# STl-Link-V01.net
KiCad netlist of a schematic drawn in EAGLE
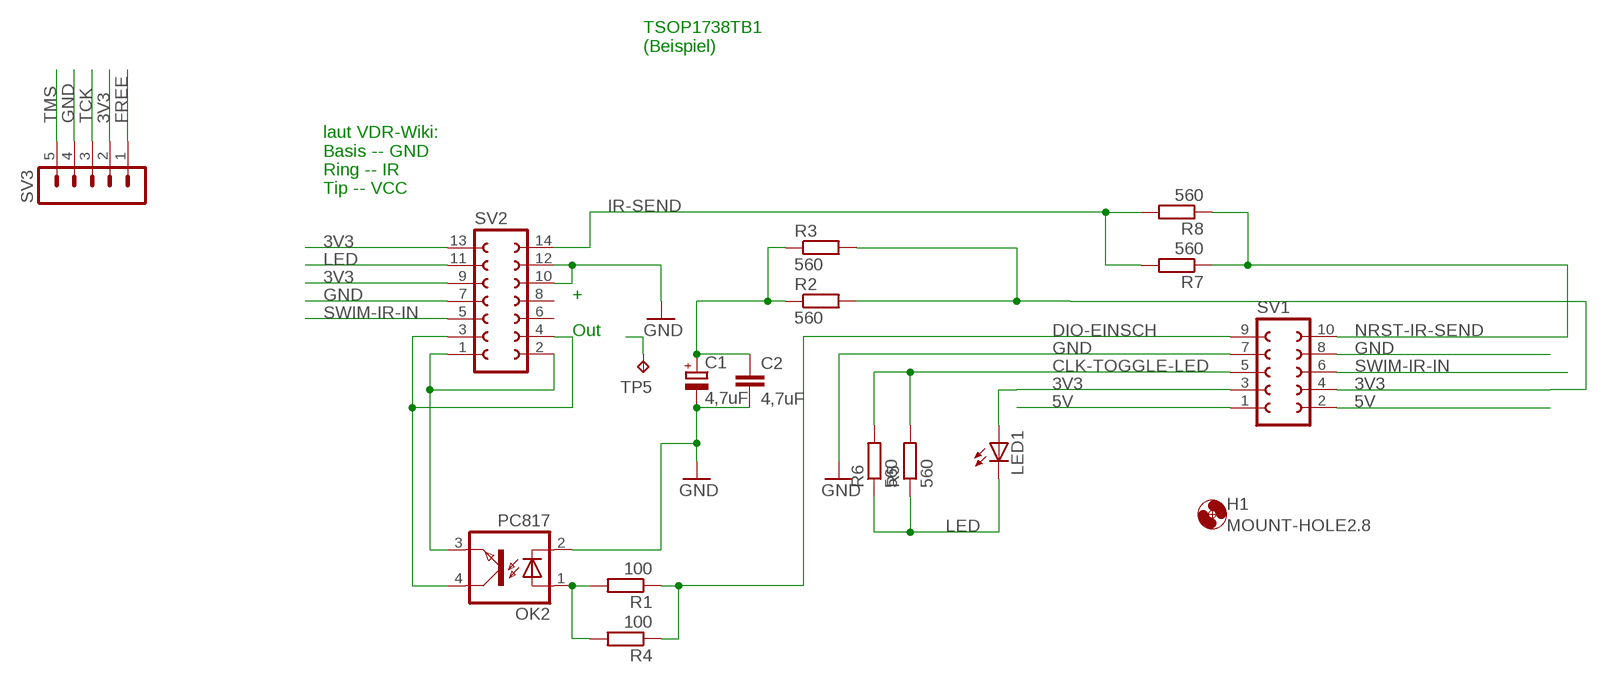
[diagram p0: schematic, sheet 1]

(export (version "E")
  (design (tool "Eeschema 10.0.6"))
  (components
    (comp (ref "C1")
      (value "4,7uF")
      (footprint "eagle-import:E1,8-4")
      (libsource (lib "eagle-import") (part "CPOL-EUE1.8-4"))
    )
    (comp (ref "C2")
      (value "4,7uF")
      (footprint "eagle-import:C1206K")
      (libsource (lib "eagle-import") (part "C-EUC1206K"))
    )
    (comp (ref "H1")
      (value "MOUNT-HOLE2.8")
      (footprint "eagle-import:2,8")
      (libsource (lib "eagle-import") (part "MOUNT-HOLE2.8"))
    )
    (comp (ref "LED1")
      (value "LEDCHIPLED_1206")
      (footprint "eagle-import:CHIPLED_1206")
      (libsource (lib "eagle-import") (part "LEDCHIPLED_1206"))
    )
    (comp (ref "OK2")
      (value "PC817")
      (footprint "eagle-import:DIL04")
      (fields (field (name "MPN") "PC817X4J000F"))
      (libsource (lib "eagle-import") (part "PC817"))
    )
    (comp (ref "R1")
      (value "100")
      (footprint "eagle-import:0204_7")
      (libsource (lib "eagle-import") (part "R-EU_0204/7"))
    )
    (comp (ref "R2")
      (value "560")
      (footprint "eagle-import:0204_7")
      (libsource (lib "eagle-import") (part "R-EU_0204/7"))
    )
    (comp (ref "R3")
      (value "560")
      (footprint "eagle-import:R0805W")
      (libsource (lib "eagle-import") (part "R-EU_R0805W"))
    )
    (comp (ref "R4")
      (value "100")
      (footprint "eagle-import:R0805W")
      (libsource (lib "eagle-import") (part "R-EU_R0805W"))
    )
    (comp (ref "R5")
      (value "560")
      (footprint "eagle-import:0204_7")
      (libsource (lib "eagle-import") (part "R-EU_0204/7"))
    )
    (comp (ref "R6")
      (value "560")
      (footprint "eagle-import:R0805W")
      (libsource (lib "eagle-import") (part "R-EU_R0805W"))
    )
    (comp (ref "R7")
      (value "560")
      (footprint "eagle-import:0204_7")
      (libsource (lib "eagle-import") (part "R-EU_0204/7"))
    )
    (comp (ref "R8")
      (value "560")
      (footprint "eagle-import:R0805W")
      (libsource (lib "eagle-import") (part "R-EU_R0805W"))
    )
    (comp (ref "SV1")
      (value "FE05-2")
      (footprint "eagle-import:FE05-2")
      (libsource (lib "eagle-import") (part "FE05-2"))
    )
    (comp (ref "SV2")
      (value "FE07-2W")
      (footprint "eagle-import:FE07-2W")
      (libsource (lib "eagle-import") (part "FE07-2W"))
    )
    (comp (ref "SV3")
      (value "MAR05-1")
      (footprint "eagle-import:MAR05-1")
      (libsource (lib "eagle-import") (part "MAR05-1"))
    )
    (comp (ref "TP5")
      (value "TPB1,27")
      (footprint "eagle-import:B1,27")
      (libsource (lib "eagle-import") (part "TPB1,27"))
    )
  )
  (nets
    (net (code "1") (name "/3V3") (class "Default")
      (node (ref "LED1") (pin "A") (pinfunction "A_A") (pintype "passive"))
      (node (ref "R2") (pin "2") (pinfunction "2_2") (pintype "passive"))
      (node (ref "R3") (pin "2") (pinfunction "2_2") (pintype "passive"))
      (node (ref "SV1") (pin "3") (pinfunction "3_3") (pintype "passive"))
      (node (ref "SV1") (pin "4") (pinfunction "4_4") (pintype "passive"))
      (node (ref "SV2") (pin "13") (pinfunction "13_13") (pintype "passive"))
      (node (ref "SV2") (pin "9") (pinfunction "9_9") (pintype "passive"))
      (node (ref "SV3") (pin "2") (pinfunction "2_2") (pintype "passive"))
    )
    (net (code "2") (name "/5V") (class "Default")
      (node (ref "SV1") (pin "1") (pinfunction "1_1") (pintype "passive"))
      (node (ref "SV1") (pin "2") (pinfunction "2_2") (pintype "passive"))
    )
    (net (code "3") (name "/CLK-TOGGLE-LED") (class "Default")
      (node (ref "R5") (pin "2") (pinfunction "2_2") (pintype "passive"))
      (node (ref "R6") (pin "2") (pinfunction "2_2") (pintype "passive"))
      (node (ref "SV1") (pin "5") (pinfunction "5_5") (pintype "passive"))
    )
    (net (code "4") (name "/DIO-EINSCH") (class "Default")
      (node (ref "R1") (pin "1") (pinfunction "1_1") (pintype "passive"))
      (node (ref "R4") (pin "1") (pinfunction "1_1") (pintype "passive"))
      (node (ref "SV1") (pin "9") (pinfunction "9_9") (pintype "passive"))
    )
    (net (code "5") (name "/FREE") (class "Default")
      (node (ref "SV3") (pin "1") (pinfunction "1_1") (pintype "passive"))
    )
    (net (code "6") (name "/IR-SEND") (class "Default")
      (node (ref "R7") (pin "2") (pinfunction "2_2") (pintype "passive"))
      (node (ref "R8") (pin "2") (pinfunction "2_2") (pintype "passive"))
      (node (ref "SV2") (pin "14") (pinfunction "14_14") (pintype "passive"))
    )
    (net (code "7") (name "/LED") (class "Default")
      (node (ref "LED1") (pin "C") (pinfunction "C_C") (pintype "passive"))
      (node (ref "R5") (pin "1") (pinfunction "1_1") (pintype "passive"))
      (node (ref "R6") (pin "1") (pinfunction "1_1") (pintype "passive"))
      (node (ref "SV2") (pin "11") (pinfunction "11_11") (pintype "passive"))
    )
    (net (code "8") (name "/NRST-IR-SEND") (class "Default")
      (node (ref "R7") (pin "1") (pinfunction "1_1") (pintype "passive"))
      (node (ref "R8") (pin "1") (pinfunction "1_1") (pintype "passive"))
      (node (ref "SV1") (pin "10") (pinfunction "10_10") (pintype "passive"))
    )
    (net (code "9") (name "/SWIM-IR-IN") (class "Default")
      (node (ref "SV1") (pin "6") (pinfunction "6_6") (pintype "passive"))
      (node (ref "SV2") (pin "5") (pinfunction "5_5") (pintype "passive"))
      (node (ref "TP5") (pin "TP") (pinfunction "TP_TP") (pintype "input"))
    )
    (net (code "10") (name "/TCK") (class "Default")
      (node (ref "SV3") (pin "3") (pinfunction "3_3") (pintype "passive"))
    )
    (net (code "11") (name "/TMS") (class "Default")
      (node (ref "SV3") (pin "5") (pinfunction "5_5") (pintype "passive"))
    )
    (net (code "12") (name "GND") (class "Default")
      (node (ref "C1") (pin "-") (pinfunction "-_-") (pintype "passive"))
      (node (ref "C2") (pin "2") (pinfunction "2_2") (pintype "passive"))
      (node (ref "OK2") (pin "2") (pinfunction "C_2") (pintype "passive"))
      (node (ref "SV1") (pin "7") (pinfunction "7_7") (pintype "passive"))
      (node (ref "SV1") (pin "8") (pinfunction "8_8") (pintype "passive"))
      (node (ref "SV2") (pin "10") (pinfunction "10_10") (pintype "passive"))
      (node (ref "SV2") (pin "12") (pinfunction "12_12") (pintype "passive"))
      (node (ref "SV2") (pin "7") (pinfunction "7_7") (pintype "passive"))
      (node (ref "SV3") (pin "4") (pinfunction "4_4") (pintype "passive"))
    )
    (net (code "13") (name "Net-(C1-Pad+)") (class "Default")
      (node (ref "C1") (pin "+") (pinfunction "+_+") (pintype "passive"))
      (node (ref "C2") (pin "1") (pinfunction "1_1") (pintype "passive"))
      (node (ref "R2") (pin "1") (pinfunction "1_1") (pintype "passive"))
      (node (ref "R3") (pin "1") (pinfunction "1_1") (pintype "passive"))
    )
    (net (code "14") (name "Net-(OK2-A)") (class "Default")
      (node (ref "OK2") (pin "1") (pinfunction "A_1") (pintype "passive"))
      (node (ref "R1") (pin "2") (pinfunction "2_2") (pintype "passive"))
      (node (ref "R4") (pin "2") (pinfunction "2_2") (pintype "passive"))
    )
    (net (code "15") (name "Net-(OK2-COL)") (class "Default")
      (node (ref "OK2") (pin "4") (pinfunction "COL_4") (pintype "passive"))
      (node (ref "SV2") (pin "3") (pinfunction "3_3") (pintype "passive"))
      (node (ref "SV2") (pin "4") (pinfunction "4_4") (pintype "passive"))
    )
    (net (code "16") (name "Net-(OK2-EMIT)") (class "Default")
      (node (ref "OK2") (pin "3") (pinfunction "EMIT_3") (pintype "passive"))
      (node (ref "SV2") (pin "1") (pinfunction "1_1") (pintype "passive"))
      (node (ref "SV2") (pin "2") (pinfunction "2_2") (pintype "passive"))
    )
    (net (code "17") (name "unconnected-(SV2-Pad6)") (class "Default")
      (node (ref "SV2") (pin "6") (pinfunction "6_6") (pintype "passive"))
    )
    (net (code "18") (name "unconnected-(SV2-Pad8)") (class "Default")
      (node (ref "SV2") (pin "8") (pinfunction "8_8") (pintype "passive"))
    )
  )
)
